# RFID_CU_Schematic.net
KiCad netlist of a schematic drawn in Altium Designer
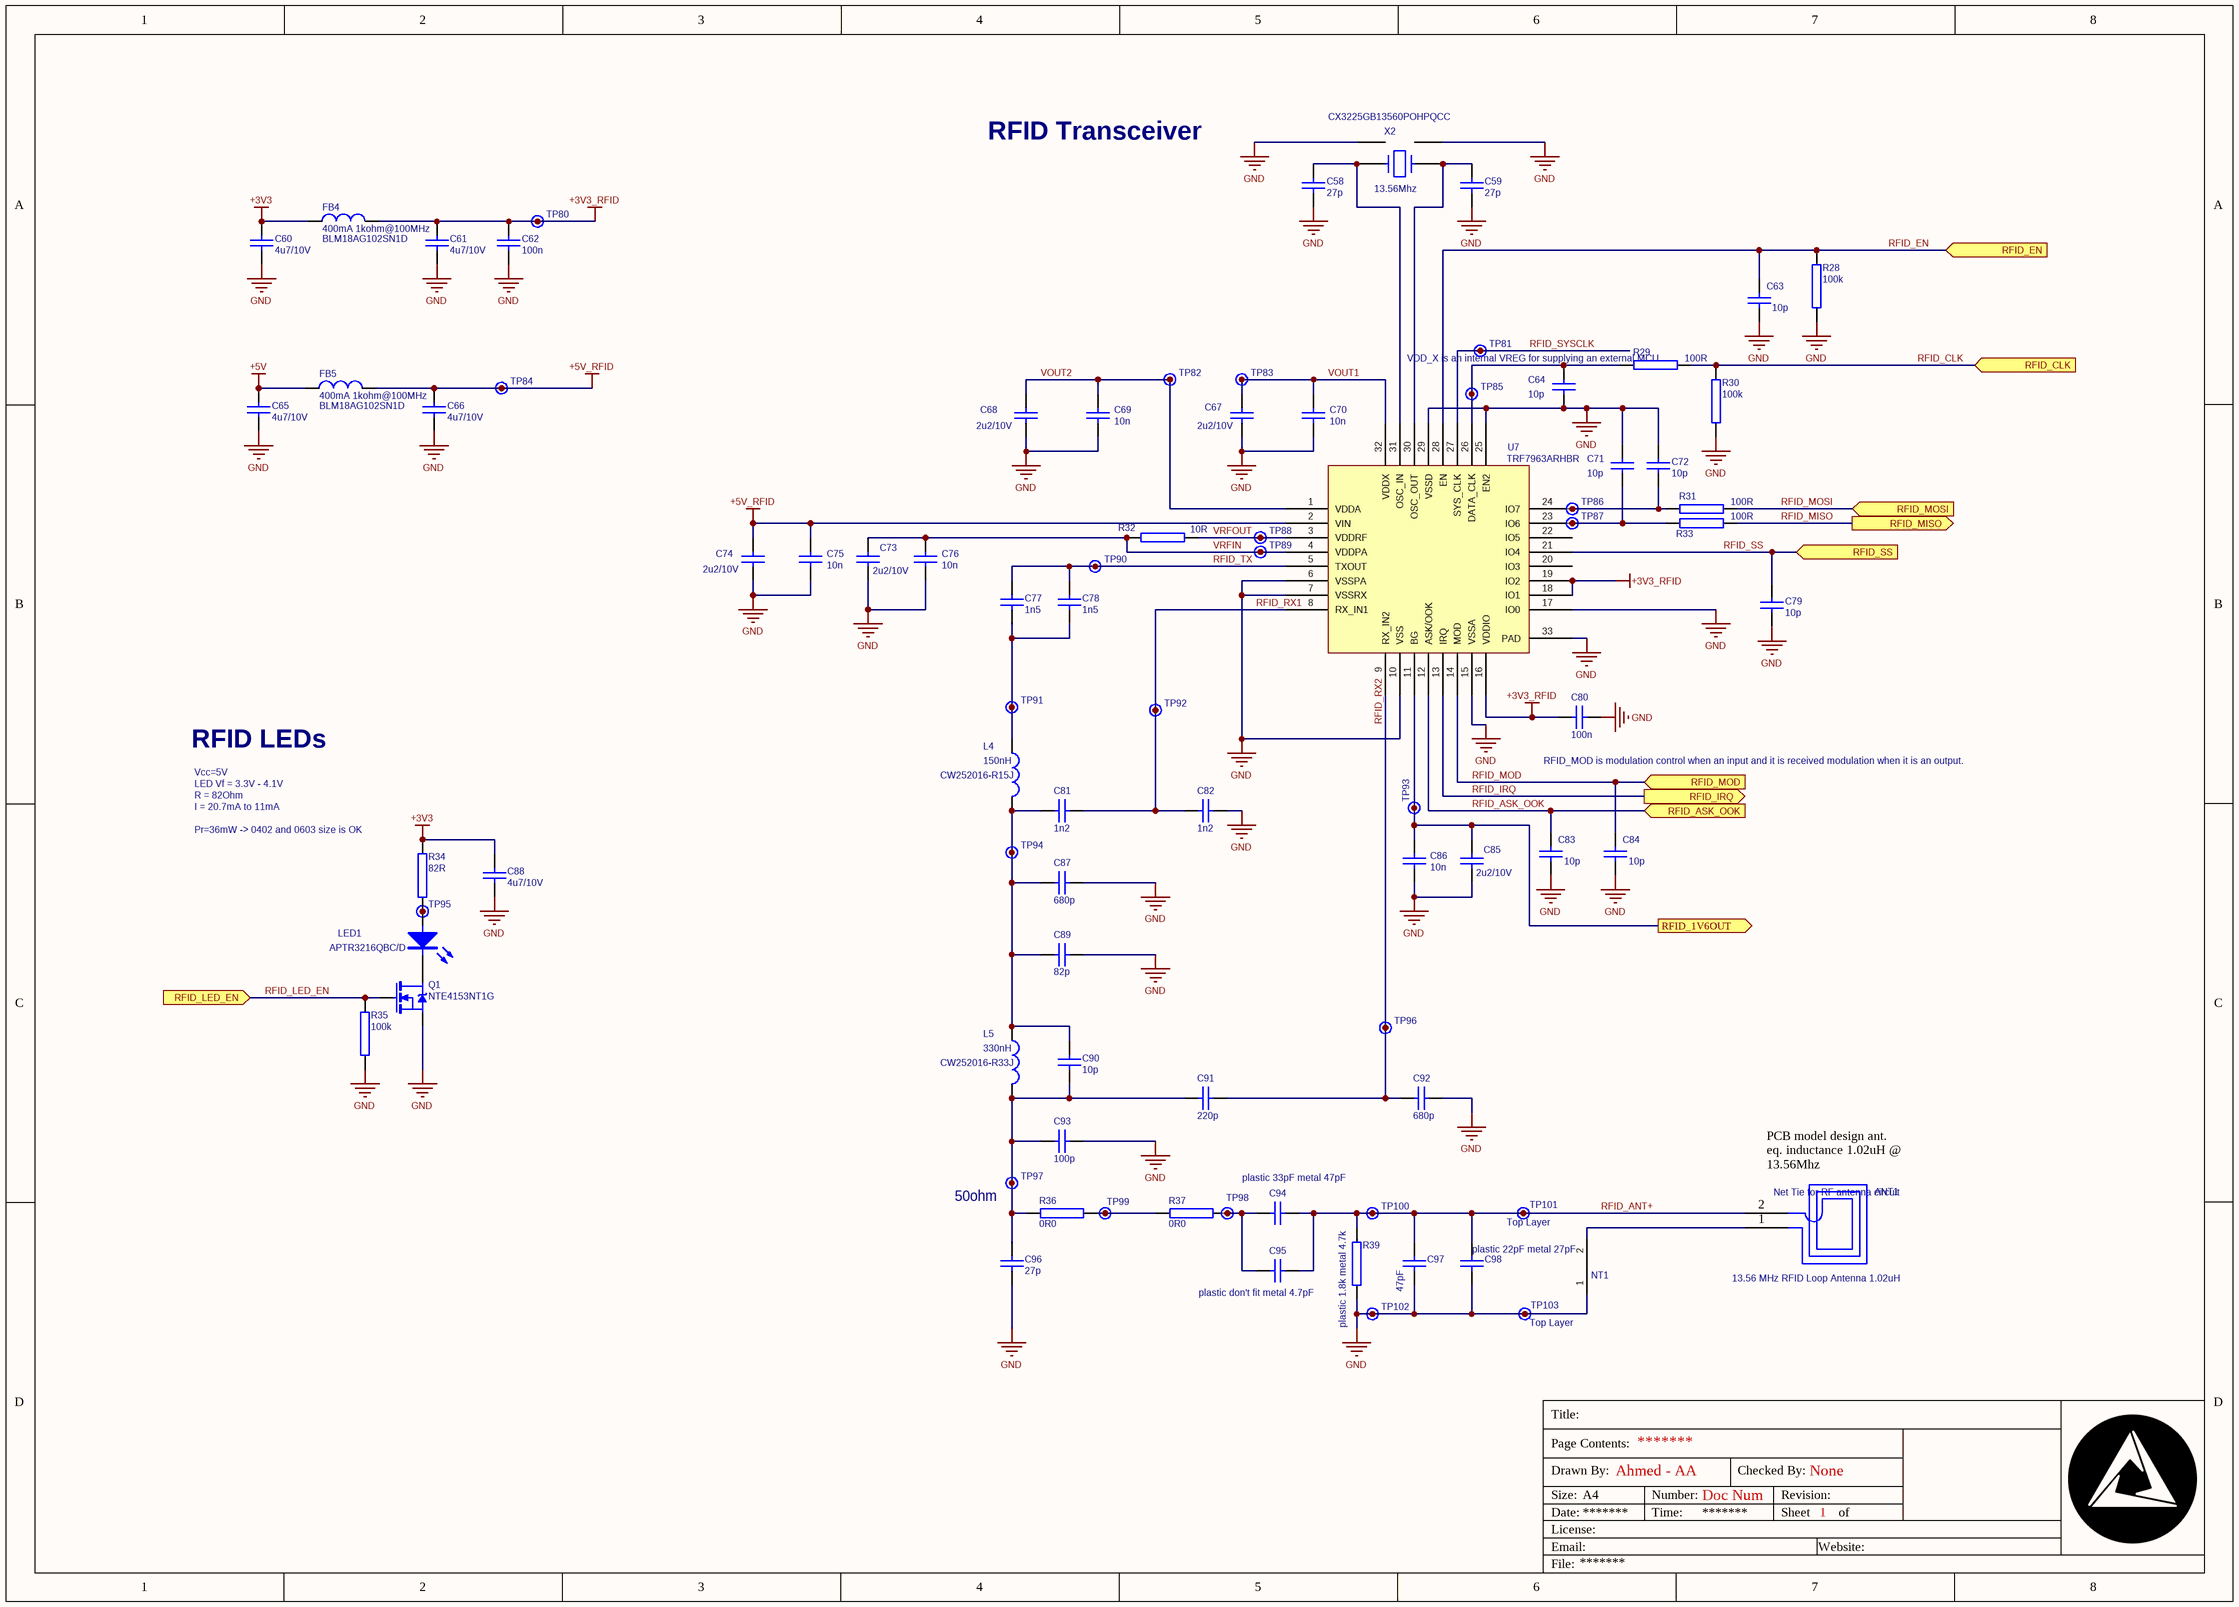
[diagram p0: RFID_CU Schematic.SchDoc]

(export (version "E")
  (design (tool "Eeschema 10.0.6"))
  (components
    (comp (ref "ANT1")
      (value "Loop Antenna")
      (footprint "RFID  Board PCB:loop_antenna")
      (description "FPC Loop Antenna")
      (fields (field (name "02 PART NUMBER") "P0000475") (field (name "12 AUTHOR") "M.Fineschi"))
      (libsource (lib "RFID Board") (part "LOOP ANT"))
    )
    (comp (ref "C58")
      (value "27p")
      (footprint "CAPC1608X09N(0603)")
      (description "Capacitor, Ceramic, 50V, Tin plated, ±1%, ±30ppm/C, C0G, 100mohm, -55°C to 125°C")
      (fields (field (name "02 PART NUMBER") "GRM1885C1H180FA01D") (field (name "12 AUTHOR") "D.Grace"))
      (libsource (lib "Miscellaneous Devices") (part "GRM1885C1H180FA01D"))
    )
    (comp (ref "C59")
      (value "27p")
      (footprint "CAPC1608X09N(0603)")
      (description "Capacitor, Ceramic, 50V, Tin plated, ±1%, ±30ppm/C, C0G, 100mohm, -55°C to 125°C")
      (fields (field (name "02 PART NUMBER") "GRM1885C1H180FA01D") (field (name "12 AUTHOR") "D.Grace"))
      (libsource (lib "Miscellaneous Devices") (part "GRM1885C1H180FA01D"))
    )
    (comp (ref "C60")
      (value "4u7/10V")
      (footprint "CAPC1608X09N(0603)")
      (description "Capacitor, Ceramic, 10V, ±10%, X5R, -55°C to 125°C")
      (fields (field (name "02 PART NUMBER") "CC0603KRX5R6BB475") (field (name "12 AUTHOR") "K.Sukumar"))
      (libsource (lib "Ingenuity Master Capacitor Schematic Library") (part "CC0603KRX5R6BB475"))
    )
    (comp (ref "C61")
      (value "4u7/10V")
      (footprint "CAPC1608X09N(0603)")
      (description "Capacitor, Ceramic, 10V, ±10%, X5R, -55°C to 125°C")
      (fields (field (name "02 PART NUMBER") "CC0603KRX5R6BB475") (field (name "12 AUTHOR") "K.Sukumar"))
      (libsource (lib "Ingenuity Master Capacitor Schematic Library") (part "CC0603KRX5R6BB475"))
    )
    (comp (ref "C62")
      (value "100n")
      (footprint "CAPC1608X09N(0603)")
      (description "Capacitor, Ceramic, 50V, ±10%, X7R, -55°C to 125°C")
      (fields (field (name "02 PART NUMBER") "GRM188R71H104KA93D") (field (name "12 AUTHOR") "D.Grace"))
      (libsource (lib "Ingenuity Master Capacitor Schematic Library") (part "GRM188R71H104KA93D"))
    )
    (comp (ref "C63")
      (value "10p")
      (footprint "CAPC1608X09N(0603)")
      (description "Capacitor, Ceramic, 50V, ±5%, NP0, -55°C to 125°C")
      (fields (field (name "02 PART NUMBER") "GQM1885C1H100JB01D") (field (name "12 AUTHOR") "M.Fineschi"))
      (libsource (lib "D0001310 Trophon EPR GUI Carrier Board Schematic Library (1_0)") (part "GQM1885C1H100JB01D"))
    )
    (comp (ref "C64")
      (value "10p")
      (footprint "CAPC1608X09N(0603)")
      (description "Capacitor, Ceramic, 50V, ±5%, NP0, -55°C to 125°C")
      (fields (field (name "02 PART NUMBER") "GQM1885C1H100JB01D") (field (name "12 AUTHOR") "M.Fineschi"))
      (libsource (lib "D0001310 Trophon EPR GUI Carrier Board Schematic Library (1_0)") (part "GQM1885C1H100JB01D"))
    )
    (comp (ref "C65")
      (value "4u7/10V")
      (footprint "CAPC1608X09N(0603)")
      (description "Capacitor, Ceramic, 10V, ±10%, X5R, -55°C to 125°C")
      (fields (field (name "02 PART NUMBER") "CC0603KRX5R6BB475") (field (name "12 AUTHOR") "K.Sukumar"))
      (libsource (lib "Ingenuity Master Capacitor Schematic Library") (part "CC0603KRX5R6BB475"))
    )
    (comp (ref "C66")
      (value "4u7/10V")
      (footprint "CAPC1608X09N(0603)")
      (description "Capacitor, Ceramic, 10V, ±10%, X5R, -55°C to 125°C")
      (fields (field (name "02 PART NUMBER") "CC0603KRX5R6BB475") (field (name "12 AUTHOR") "K.Sukumar"))
      (libsource (lib "Ingenuity Master Capacitor Schematic Library") (part "CC0603KRX5R6BB475"))
    )
    (comp (ref "C67")
      (value "2u2/10V")
      (footprint "CAPC1608X09N(0603)")
      (description "Capacitor, Ceramic, 10V, ±10%, X7R, -55°C to 125°C")
      (fields (field (name "02 PART NUMBER") "GRM188R71A225KE15D") (field (name "12 AUTHOR") "D.Grace"))
      (libsource (lib "Ingenuity Master Capacitor Schematic Library") (part "GRM188R71A225KE15D"))
    )
    (comp (ref "C68")
      (value "2u2/10V")
      (footprint "CAPC1608X09N(0603)")
      (description "Capacitor, Ceramic, 10V, ±10%, X7R, -55°C to 125°C")
      (fields (field (name "02 PART NUMBER") "GRM188R71A225KE15D") (field (name "12 AUTHOR") "D.Grace"))
      (libsource (lib "Ingenuity Master Capacitor Schematic Library") (part "GRM188R71A225KE15D"))
    )
    (comp (ref "C69")
      (value "10n")
      (footprint "CAPC1608X09N(0603)")
      (description "Capacitor, Ceramic, 50V, ±10%, X7R, -55°C to 125°C")
      (fields (field (name "02 PART NUMBER") "GRM188R71H103KA01D") (field (name "12 AUTHOR") "D.Grace"))
      (libsource (lib "Ingenuity Master Capacitor Schematic Library") (part "GRM188R71H103KA01D"))
    )
    (comp (ref "C70")
      (value "10n")
      (footprint "CAPC1608X09N(0603)")
      (description "Capacitor, Ceramic, 50V, ±10%, X7R, -55°C to 125°C")
      (fields (field (name "02 PART NUMBER") "GRM188R71H103KA01D") (field (name "12 AUTHOR") "D.Grace"))
      (libsource (lib "Ingenuity Master Capacitor Schematic Library") (part "GRM188R71H103KA01D"))
    )
    (comp (ref "C71")
      (value "10p")
      (footprint "CAPC1608X09N(0603)")
      (description "Capacitor, Ceramic, 50V, ±5%, NP0, -55°C to 125°C")
      (fields (field (name "02 PART NUMBER") "GQM1885C1H100JB01D") (field (name "12 AUTHOR") "M.Fineschi"))
      (libsource (lib "D0001310 Trophon EPR GUI Carrier Board Schematic Library (1_0)") (part "GQM1885C1H100JB01D"))
    )
    (comp (ref "C72")
      (value "10p")
      (footprint "CAPC1608X09N(0603)")
      (description "Capacitor, Ceramic, 50V, ±5%, NP0, -55°C to 125°C")
      (fields (field (name "02 PART NUMBER") "GQM1885C1H100JB01D") (field (name "12 AUTHOR") "M.Fineschi"))
      (libsource (lib "D0001310 Trophon EPR GUI Carrier Board Schematic Library (1_0)") (part "GQM1885C1H100JB01D"))
    )
    (comp (ref "C73")
      (value "2u2/10V")
      (footprint "CAPC1608X09N(0603)")
      (description "Capacitor, Ceramic, 10V, ±10%, X7R, -55°C to 125°C")
      (fields (field (name "02 PART NUMBER") "GRM188R71A225KE15D") (field (name "12 AUTHOR") "D.Grace"))
      (libsource (lib "Ingenuity Master Capacitor Schematic Library") (part "GRM188R71A225KE15D"))
    )
    (comp (ref "C74")
      (value "2u2/10V")
      (footprint "CAPC1608X09N(0603)")
      (description "Capacitor, Ceramic, 10V, ±10%, X7R, -55°C to 125°C")
      (fields (field (name "02 PART NUMBER") "GRM188R71A225KE15D") (field (name "12 AUTHOR") "D.Grace"))
      (libsource (lib "Ingenuity Master Capacitor Schematic Library") (part "GRM188R71A225KE15D"))
    )
    (comp (ref "C75")
      (value "10n")
      (footprint "CAPC1608X09N(0603)")
      (description "Capacitor, Ceramic, 50V, ±10%, X7R, -55°C to 125°C")
      (fields (field (name "02 PART NUMBER") "GRM188R71H103KA01D") (field (name "12 AUTHOR") "D.Grace"))
      (libsource (lib "Ingenuity Master Capacitor Schematic Library") (part "GRM188R71H103KA01D"))
    )
    (comp (ref "C76")
      (value "10n")
      (footprint "CAPC1608X09N(0603)")
      (description "Capacitor, Ceramic, 50V, ±10%, X7R, -55°C to 125°C")
      (fields (field (name "02 PART NUMBER") "GRM188R71H103KA01D") (field (name "12 AUTHOR") "D.Grace"))
      (libsource (lib "Ingenuity Master Capacitor Schematic Library") (part "GRM188R71H103KA01D"))
    )
    (comp (ref "C77")
      (value "1n5")
      (footprint "CAPC1608X09N(0603)")
      (description "Capacitor, Ceramic, 50V, ±10%, X7R, -55°C to 125°C")
      (fields (field (name "02 PART NUMBER") "GRM188R71H152KA01D") (field (name "12 AUTHOR") "M.Fineschi"))
      (libsource (lib "D0001310 Trophon EPR GUI Carrier Board Schematic Library (1_0)") (part "GRM188R71H152KA01D"))
    )
    (comp (ref "C78")
      (value "1n5")
      (footprint "CAPC1608X09N(0603)")
      (description "Capacitor, Ceramic, 50V, ±10%, X7R, -55°C to 125°C")
      (fields (field (name "02 PART NUMBER") "GRM188R71H152KA01D") (field (name "12 AUTHOR") "M.Fineschi"))
      (libsource (lib "D0001310 Trophon EPR GUI Carrier Board Schematic Library (1_0)") (part "GRM188R71H152KA01D"))
    )
    (comp (ref "C79")
      (value "10p")
      (footprint "CAPC1608X09N(0603)")
      (description "Capacitor, Ceramic, 50V, ±5%, NP0, -55°C to 125°C")
      (fields (field (name "02 PART NUMBER") "GQM1885C1H100JB01D") (field (name "12 AUTHOR") "M.Fineschi"))
      (libsource (lib "D0001310 Trophon EPR GUI Carrier Board Schematic Library (1_0)") (part "GQM1885C1H100JB01D"))
    )
    (comp (ref "C80")
      (value "100n")
      (footprint "CAPC1608X09N(0603)")
      (description "Capacitor, Ceramic, 50V, ±10%, X7R, -55°C to 125°C")
      (fields (field (name "02 PART NUMBER") "GRM188R71H104KA93D") (field (name "12 AUTHOR") "D.Grace"))
      (libsource (lib "Ingenuity Master Capacitor Schematic Library") (part "GRM188R71H104KA93D"))
    )
    (comp (ref "C81")
      (value "1n2")
      (footprint "CAPC1608X09N(0603)")
      (description "Capacitor, Ceramic, 50V, ±10%, X7R, -55°C to 125°C")
      (fields (field (name "02 PART NUMBER") "GRM188R71H122KA01D") (field (name "12 AUTHOR") "M.Fineschi"))
      (libsource (lib "D0001310 Trophon EPR GUI Carrier Board Schematic Library (1_0)") (part "GRM188R71H122KA01D"))
    )
    (comp (ref "C82")
      (value "1n2")
      (footprint "CAPC1608X09N(0603)")
      (description "Capacitor, Ceramic, 50V, ±10%, X7R, -55°C to 125°C")
      (fields (field (name "02 PART NUMBER") "GRM188R71H122KA01D") (field (name "12 AUTHOR") "M.Fineschi"))
      (libsource (lib "D0001310 Trophon EPR GUI Carrier Board Schematic Library (1_0)") (part "GRM188R71H122KA01D"))
    )
    (comp (ref "C83")
      (value "10p")
      (footprint "CAPC1608X09N(0603)")
      (description "Capacitor, Ceramic, 50V, ±5%, NP0, -55°C to 125°C")
      (fields (field (name "02 PART NUMBER") "GQM1885C1H100JB01D") (field (name "12 AUTHOR") "M.Fineschi"))
      (libsource (lib "D0001310 Trophon EPR GUI Carrier Board Schematic Library (1_0)") (part "GQM1885C1H100JB01D"))
    )
    (comp (ref "C84")
      (value "10p")
      (footprint "CAPC1608X09N(0603)")
      (description "Capacitor, Ceramic, 50V, ±5%, NP0, -55°C to 125°C")
      (fields (field (name "02 PART NUMBER") "GQM1885C1H100JB01D") (field (name "12 AUTHOR") "M.Fineschi"))
      (libsource (lib "D0001310 Trophon EPR GUI Carrier Board Schematic Library (1_0)") (part "GQM1885C1H100JB01D"))
    )
    (comp (ref "C85")
      (value "2u2/10V")
      (footprint "CAPC1608X09N(0603)")
      (description "Capacitor, Ceramic, 10V, ±10%, X7R, -55°C to 125°C")
      (fields (field (name "02 PART NUMBER") "GRM188R71A225KE15D") (field (name "12 AUTHOR") "D.Grace"))
      (libsource (lib "Ingenuity Master Capacitor Schematic Library") (part "GRM188R71A225KE15D"))
    )
    (comp (ref "C86")
      (value "10n")
      (footprint "CAPC1608X09N(0603)")
      (description "Capacitor, Ceramic, 50V, ±10%, X7R, -55°C to 125°C")
      (fields (field (name "02 PART NUMBER") "GRM188R71H103KA01D") (field (name "12 AUTHOR") "D.Grace"))
      (libsource (lib "Ingenuity Master Capacitor Schematic Library") (part "GRM188R71H103KA01D"))
    )
    (comp (ref "C87")
      (value "680p")
      (footprint "CAPC1608X09N(0603)")
      (description "Capacitor, Ceramic, 50V, ±10%, X7R, -55°C to 125°C")
      (fields (field (name "02 PART NUMBER") "GRM188R71H681KA01D") (field (name "12 AUTHOR") "M.Fineschi"))
      (libsource (lib "D0001310 Trophon EPR GUI Carrier Board Schematic Library (1_0)") (part "GRM188R71H681KA01D"))
    )
    (comp (ref "C88")
      (value "4u7/10V")
      (footprint "CAPC1608X09N(0603)")
      (description "Capacitor, Ceramic, 10V, ±10%, X5R, -55°C to 125°C")
      (fields (field (name "02 PART NUMBER") "CC0603KRX5R6BB475") (field (name "12 AUTHOR") "K.Sukumar"))
      (libsource (lib "Ingenuity Master Capacitor Schematic Library") (part "CC0603KRX5R6BB475"))
    )
    (comp (ref "C89")
      (value "82p")
      (footprint "CAPC1608X09N(0603)")
      (description "Capacitor, Ceramic, 50V, ±5%, NP0, -55°C to 125°C")
      (fields (field (name "02 PART NUMBER") "GRM1885C1H820JA01D") (field (name "12 AUTHOR") "M.Fineschi"))
      (libsource (lib "D0001310 Trophon EPR GUI Carrier Board Schematic Library (1_0)") (part "GRM1885C1H820JA01D"))
    )
    (comp (ref "C90")
      (value "10p")
      (footprint "CAPC1608X09N(0603)")
      (description "Capacitor, Ceramic, 50V, ±5%, NP0, -55°C to 125°C")
      (fields (field (name "02 PART NUMBER") "GQM1885C1H100JB01D") (field (name "12 AUTHOR") "M.Fineschi"))
      (libsource (lib "D0001310 Trophon EPR GUI Carrier Board Schematic Library (1_0)") (part "GQM1885C1H100JB01D"))
    )
    (comp (ref "C91")
      (value "220p")
      (footprint "CAPC1608X09N(0603)")
      (description "Capacitor, Ceramic, 50V, ±10%, X7R, -55°C to 125°C")
      (fields (field (name "02 PART NUMBER") "GRM188R71H221KA01D") (field (name "12 AUTHOR") "M.Fineschi"))
      (libsource (lib "D0001310 Trophon EPR GUI Carrier Board Schematic Library (1_0)") (part "GRM188R71H221KA01D"))
    )
    (comp (ref "C92")
      (value "680p")
      (footprint "CAPC1608X09N(0603)")
      (description "Capacitor, Ceramic, 50V, ±10%, X7R, -55°C to 125°C")
      (fields (field (name "02 PART NUMBER") "GRM188R71H681KA01D") (field (name "12 AUTHOR") "M.Fineschi"))
      (libsource (lib "D0001310 Trophon EPR GUI Carrier Board Schematic Library (1_0)") (part "GRM188R71H681KA01D"))
    )
    (comp (ref "C93")
      (value "100p")
      (footprint "CAPC1608X09N(0603)")
      (description "Capacitor, Ceramic, 50V, ±5%, C0G NP0, -55°C to 125°C")
      (fields (field (name "02 PART NUMBER") "GRM1885C1H101JA01D") (field (name "12 AUTHOR") "D.Grace"))
      (libsource (lib "Ingenuity Master Capacitor Schematic Library") (part "GRM1885C1H101JA01D"))
    )
    (comp (ref "C94")
      (value "plastic 33pF metal 47pF")
      (footprint "CAPC1608X09N(0603)")
      (description "Capacitor, Ceramic, 50V, ±5%, NP0, -55°C to 125°C")
      (fields (field (name "02 PART NUMBER") "GRM1885C1H470JA01D") (field (name "12 AUTHOR") "M.Fineschi"))
      (libsource (lib "D0001310 Trophon EPR GUI Carrier Board Schematic Library (1_0)") (part "GRM1885C1H470JA01D"))
    )
    (comp (ref "C95")
      (value "plastic don't fit metal 4.7pF")
      (footprint "CAPC1608X09N(0603)")
      (description "Capacitor, Ceramic, 50V, ±5%, NP0, -55°C to 125°C")
      (fields (field (name "02 PART NUMBER") "GQM1885C1H100JB01D") (field (name "12 AUTHOR") "M.Fineschi"))
      (libsource (lib "D0001310 Trophon EPR GUI Carrier Board Schematic Library (1_0)") (part "GQM1885C1H100JB01D"))
    )
    (comp (ref "C96")
      (value "27p")
      (footprint "CAPC1608X09N(0603)")
      (description "Capacitor, Ceramic, 50V, ±5%, NP0, -55°C to 125°C")
      (fields (field (name "02 PART NUMBER") "GRM1885C1H270JA01D") (field (name "12 AUTHOR") "M.Fineschi"))
      (libsource (lib "D0001310 Trophon EPR GUI Carrier Board Schematic Library (1_0)") (part "GRM1885C1H270JA01D"))
    )
    (comp (ref "C97")
      (value "47pF")
      (footprint "CAPC1608X09N(0603)")
      (description "Capacitor, Ceramic, 50V, ±5%, NP0, -55°C to 125°C")
      (fields (field (name "02 PART NUMBER") "GRM1885C1H820JA01D") (field (name "12 AUTHOR") "M.Fineschi"))
      (libsource (lib "D0001310 Trophon EPR GUI Carrier Board Schematic Library (1_0)") (part "GRM1885C1H820JA01D"))
    )
    (comp (ref "C98")
      (value "plastic 22pF metal 27pF")
      (footprint "CAPC1608X09N(0603)")
      (description "Capacitor, Ceramic, 50V, ±5%, C0G NP0, -55°C to 125°C")
      (fields (field (name "02 PART NUMBER") "GRM1885C1H101JA01D") (field (name "12 AUTHOR") "D.Grace"))
      (libsource (lib "Ingenuity Master Capacitor Schematic Library") (part "GRM1885C1H101JA01D"))
    )
    (comp (ref "FB4")
      (value "400mA 1kohm@100MHz")
      (footprint "RESC1608X06N")
      (description "Ferrite Bead, 1kohm@100MHz, 400mA, 500mohm, -55 to 125C")
      (fields (field (name "02 PART NUMBER") "BLM18AG102SN1D") (field (name "12 AUTHOR") "M.Fineschi"))
      (libsource (lib "D0000174 Puck Charger Schematic Library (1_6)") (part "BLM18AG102SN1D"))
    )
    (comp (ref "FB5")
      (value "400mA 1kohm@100MHz")
      (footprint "RESC1608X06N")
      (description "Ferrite Bead, 1kohm@100MHz, 400mA, 500mohm, -55 to 125C")
      (fields (field (name "02 PART NUMBER") "BLM18AG102SN1D") (field (name "12 AUTHOR") "M.Fineschi"))
      (libsource (lib "D0000174 Puck Charger Schematic Library (1_6)") (part "BLM18AG102SN1D"))
    )
    (comp (ref "L4")
      (value "150nH")
      (footprint "CW252016")
      (description "Inductor, 150nH , I = 500mA, 220 mOhm, SRF 850MHz, ±5%")
      (fields
        (field (name "02 PART NUMBER") "CW252016-R15J")
        (field (name "12 AUTHOR") "D.Grace")
        (field (name "13 REVIEWED BY") "P.Moutzouris")
      )
      (libsource (lib "Ingenuity Master Inductors Schematic Library") (part "CW252016-R15J_PA"))
    )
    (comp (ref "L5")
      (value "330nH")
      (footprint "CW252016")
      (description "Inductor, 330nH , I = 500mA, 900 mOhm, SRF 570MHz, ±5%")
      (fields
        (field (name "02 PART NUMBER") "CW252016-R33J")
        (field (name "12 AUTHOR") "D.Grace")
        (field (name "13 REVIEWED BY") "P.Moutzouris")
      )
      (libsource (lib "Ingenuity Master Inductors Schematic Library") (part "CW252016-R33J_PA"))
    )
    (comp (ref "LED1")
      (value "APTR3216QBC/D")
      (footprint "APTR3216QBC/D")
      (description "LED, TopEntry, Blue, 4000mcd, 20mA, Vf=3V3")
      (fields (field (name "12 AUTHOR") "M.Fineschi"))
      (libsource (lib "D0001310 Trophon EPR GUI Carrier Board Altium Project (1_4)") (part "KPTR-3216ZGC"))
    )
    (comp (ref "NT1")
      (value "Net Tie")
      (footprint "0.15mm Net Tie")
      (libsource (lib "D0001231 Lock-It Smart Cabinet Panel Schematic Library") (part "Net Tie"))
    )
    (comp (ref "Q1")
      (value "NTE4153NT1G")
      (footprint "SC-89")
      (description "MOSFET, N-Channel, Logic Level, 0.5Ohm @ 1.5V, Vds 50V, Id 915mA, 300mW")
      (fields (field (name "12 AUTHOR") "D.Grace"))
      (libsource (lib "Ingenuity Master Transistors Schematic Library") (part "NTE4153NT1G"))
    )
    (comp (ref "R28")
      (value "100k")
      (footprint "RESC1608X06N(0603)")
      (description "Resistor, Thick Film, 0.1W, ±1%, ±100ppm/°C")
      (fields
        (field (name "02 PART NUMBER") "RC0603FR-07100KL")
        (field (name "13 REVIEWED BY") "P.Moutzouris")
        (field (name "12 AUTHOR") "D.Grace")
      )
      (libsource (lib "Ingenuity Master Resistor 0603 Schematic Library") (part "RC0603FR-07100KL"))
    )
    (comp (ref "R29")
      (value "100R")
      (footprint "RESC1608X06N(0603)")
      (description "Resistor, Thick Film, 0.1W, ±1%, ±100ppm/°C")
      (fields
        (field (name "02 PART NUMBER") "RC0603FR-07100RL")
        (field (name "13 REVIEWED BY") "P.Moutzouris")
        (field (name "12 AUTHOR") "D.Grace")
      )
      (libsource (lib "Ingenuity Master Resistor 0603 Schematic Library") (part "RC0603FR-07100RL"))
    )
    (comp (ref "R30")
      (value "100k")
      (footprint "RESC1608X06N(0603)")
      (description "Resistor, Thick Film, 0.1W, ±1%, ±100ppm/°C")
      (fields
        (field (name "02 PART NUMBER") "RC0603FR-07100KL")
        (field (name "13 REVIEWED BY") "P.Moutzouris")
        (field (name "12 AUTHOR") "D.Grace")
      )
      (libsource (lib "Ingenuity Master Resistor 0603 Schematic Library") (part "RC0603FR-07100KL"))
    )
    (comp (ref "R31")
      (value "100R")
      (footprint "RESC1608X06N(0603)")
      (description "Resistor, Thick Film, 0.1W, ±1%, ±100ppm/°C")
      (fields
        (field (name "02 PART NUMBER") "RC0603FR-07100RL")
        (field (name "13 REVIEWED BY") "P.Moutzouris")
        (field (name "12 AUTHOR") "D.Grace")
      )
      (libsource (lib "Ingenuity Master Resistor 0603 Schematic Library") (part "RC0603FR-07100RL"))
    )
    (comp (ref "R32")
      (value "10R")
      (footprint "RESC1608X06N(0603)")
      (description "Resistor, Thick Film, 0.1W, ±1%, ±100ppm/°C")
      (fields (field (name "02 PART NUMBER") "RC0603FR-0710RL") (field (name "12 AUTHOR") "M.Fineschi"))
      (libsource (lib "D0001310 Trophon EPR GUI Carrier Board Schematic Library (1_0)") (part "RC0603FR-0710RL"))
    )
    (comp (ref "R33")
      (value "100R")
      (footprint "RESC1608X06N(0603)")
      (description "Resistor, Thick Film, 0.1W, ±1%, ±100ppm/°C")
      (fields
        (field (name "02 PART NUMBER") "RC0603FR-07100RL")
        (field (name "13 REVIEWED BY") "P.Moutzouris")
        (field (name "12 AUTHOR") "D.Grace")
      )
      (libsource (lib "Ingenuity Master Resistor 0603 Schematic Library") (part "RC0603FR-07100RL"))
    )
    (comp (ref "R34")
      (value "82R")
      (footprint "RESC1608X06N(0603)")
      (description "Resistor, Thick Film, 0.1W, ±1%, ±100ppm/°C")
      (fields
        (field (name "02 PART NUMBER") "RC0603FR-0782RL")
        (field (name "13 REVIEWED BY") "P.Moutzouris")
        (field (name "12 AUTHOR") "D.Grace")
      )
      (libsource (lib "D0001310 Trophon EPR GUI Carrier Board Altium Project (1_4)") (part "RC0603FR-0782RL"))
    )
    (comp (ref "R35")
      (value "100k")
      (footprint "RESC1608X06N(0603)")
      (description "Resistor, Thick Film, 0.1W, ±1%, ±100ppm/°C")
      (fields
        (field (name "02 PART NUMBER") "RC0603FR-07100KL")
        (field (name "13 REVIEWED BY") "P.Moutzouris")
        (field (name "12 AUTHOR") "D.Grace")
      )
      (libsource (lib "Ingenuity Master Resistor 0603 Schematic Library") (part "RC0603FR-07100KL"))
    )
    (comp (ref "R36")
      (value "0R0")
      (footprint "RESC1608X06N(0603)")
      (description "Resistor, Thick Film, 0.1W, ±1%, ±100ppm/°C")
      (fields
        (field (name "02 PART NUMBER") "RC1608J000CS")
        (field (name "13 REVIEWED BY") "P.Moutzouris")
        (field (name "12 AUTHOR") "K.Sukumar")
      )
      (libsource (lib "Ingenuity Master Resistor 0603 Schematic Library") (part "RC1608J000CS"))
    )
    (comp (ref "R37")
      (value "0R0")
      (footprint "RESC1608X06N(0603)")
      (description "Resistor, Thick Film, 0.1W, ±1%, ±100ppm/°C")
      (fields
        (field (name "02 PART NUMBER") "RC1608J000CS")
        (field (name "13 REVIEWED BY") "P.Moutzouris")
        (field (name "12 AUTHOR") "K.Sukumar")
      )
      (libsource (lib "Ingenuity Master Resistor 0603 Schematic Library") (part "RC1608J000CS"))
    )
    (comp (ref "R39")
      (value "plastic 1.8k metal 4.7k")
      (footprint "RESC1608X06N(0603)")
      (description "Resistor, Thick Film, 0.1W, ±1%, ±100ppm/°C")
      (fields
        (field (name "02 PART NUMBER") "RC0603FR-071KL")
        (field (name "13 REVIEWED BY") "P.Moutzouris")
        (field (name "12 AUTHOR") "D.Grace")
      )
      (libsource (lib "Ingenuity Master Resistor 0603 Schematic Library") (part "RC0603FR-071KL"))
    )
    (comp (ref "TP80")
      (value "LFX_P")
      (footprint "Test Point 1mm")
      (description "Test Point")
      (fields (field (name "12 AUTHOR") "D.Grace"))
      (libsource (lib "Mesh Nebuliser Schematic Library") (part "Test Point"))
    )
    (comp (ref "TP81")
      (value "LFX_P")
      (footprint "Test Point 1mm")
      (description "Test Point")
      (fields (field (name "12 AUTHOR") "D.Grace"))
      (libsource (lib "Mesh Nebuliser Schematic Library") (part "Test Point"))
    )
    (comp (ref "TP82")
      (value "LFX_P")
      (footprint "Test Point 1mm")
      (description "Test Point")
      (fields (field (name "12 AUTHOR") "D.Grace"))
      (libsource (lib "Mesh Nebuliser Schematic Library") (part "Test Point"))
    )
    (comp (ref "TP83")
      (value "LFX_P")
      (footprint "Test Point 1mm")
      (description "Test Point")
      (fields (field (name "12 AUTHOR") "D.Grace"))
      (libsource (lib "Mesh Nebuliser Schematic Library") (part "Test Point"))
    )
    (comp (ref "TP84")
      (value "LFX_P")
      (footprint "Test Point 1mm")
      (description "Test Point")
      (fields (field (name "12 AUTHOR") "D.Grace"))
      (libsource (lib "Mesh Nebuliser Schematic Library") (part "Test Point"))
    )
    (comp (ref "TP85")
      (value "LFX_P")
      (footprint "Test Point 1mm")
      (description "Test Point")
      (fields (field (name "12 AUTHOR") "D.Grace"))
      (libsource (lib "Mesh Nebuliser Schematic Library") (part "Test Point"))
    )
    (comp (ref "TP86")
      (value "LFX_P")
      (footprint "Test Point 1mm")
      (description "Test Point")
      (fields (field (name "12 AUTHOR") "D.Grace"))
      (libsource (lib "Mesh Nebuliser Schematic Library") (part "Test Point"))
    )
    (comp (ref "TP87")
      (value "LFX_P")
      (footprint "Test Point 1mm")
      (description "Test Point")
      (fields (field (name "12 AUTHOR") "D.Grace"))
      (libsource (lib "Mesh Nebuliser Schematic Library") (part "Test Point"))
    )
    (comp (ref "TP88")
      (value "LFX_P")
      (footprint "Test Point 1mm")
      (description "Test Point")
      (fields (field (name "12 AUTHOR") "D.Grace"))
      (libsource (lib "Mesh Nebuliser Schematic Library") (part "Test Point"))
    )
    (comp (ref "TP89")
      (value "LFX_P")
      (footprint "Test Point 1mm")
      (description "Test Point")
      (fields (field (name "12 AUTHOR") "D.Grace"))
      (libsource (lib "Mesh Nebuliser Schematic Library") (part "Test Point"))
    )
    (comp (ref "TP90")
      (value "LFX_P")
      (footprint "Test Point 1mm")
      (description "Test Point")
      (fields (field (name "12 AUTHOR") "D.Grace"))
      (libsource (lib "Mesh Nebuliser Schematic Library") (part "Test Point"))
    )
    (comp (ref "TP91")
      (value "LFX_P")
      (footprint "Test Point 1mm")
      (description "Test Point")
      (fields (field (name "12 AUTHOR") "D.Grace"))
      (libsource (lib "Mesh Nebuliser Schematic Library") (part "Test Point"))
    )
    (comp (ref "TP92")
      (value "LFX_P")
      (footprint "Test Point 1mm")
      (description "Test Point")
      (fields (field (name "12 AUTHOR") "D.Grace"))
      (libsource (lib "Mesh Nebuliser Schematic Library") (part "Test Point"))
    )
    (comp (ref "TP93")
      (value "LFX_P")
      (footprint "Test Point 1mm")
      (description "Test Point")
      (fields (field (name "12 AUTHOR") "D.Grace"))
      (libsource (lib "Mesh Nebuliser Schematic Library") (part "Test Point"))
    )
    (comp (ref "TP94")
      (value "LFX_P")
      (footprint "Test Point 1mm")
      (description "Test Point")
      (fields (field (name "12 AUTHOR") "D.Grace"))
      (libsource (lib "Mesh Nebuliser Schematic Library") (part "Test Point"))
    )
    (comp (ref "TP95")
      (value "LFX_P")
      (footprint "Test Point 1mm")
      (description "Test Point")
      (fields (field (name "12 AUTHOR") "D.Grace"))
      (libsource (lib "Mesh Nebuliser Schematic Library") (part "Test Point"))
    )
    (comp (ref "TP96")
      (value "LFX_P")
      (footprint "Test Point 1mm")
      (description "Test Point")
      (fields (field (name "12 AUTHOR") "D.Grace"))
      (libsource (lib "Mesh Nebuliser Schematic Library") (part "Test Point"))
    )
    (comp (ref "TP97")
      (value "50ohm")
      (footprint "Test Point 1mm")
      (description "Test Point")
      (fields (field (name "12 AUTHOR") "D.Grace"))
      (libsource (lib "Mesh Nebuliser Schematic Library") (part "Test Point"))
    )
    (comp (ref "TP98")
      (value "LFX_P")
      (footprint "Test Point 1mm")
      (description "Test Point")
      (fields (field (name "12 AUTHOR") "D.Grace"))
      (libsource (lib "Mesh Nebuliser Schematic Library") (part "Test Point"))
    )
    (comp (ref "TP99")
      (value "LFX_P")
      (footprint "Test Point 1mm")
      (description "Test Point")
      (fields (field (name "12 AUTHOR") "D.Grace"))
      (libsource (lib "Mesh Nebuliser Schematic Library") (part "Test Point"))
    )
    (comp (ref "TP100")
      (value "LFX_P")
      (footprint "Test Point 1mm")
      (description "Test Point")
      (fields (field (name "12 AUTHOR") "D.Grace"))
      (libsource (lib "Mesh Nebuliser Schematic Library") (part "Test Point"))
    )
    (comp (ref "TP101")
      (value "LFX_P")
      (footprint "Test Point 1mm")
      (description "Test Point")
      (fields (field (name "NOTES") "Top Layer") (field (name "12 AUTHOR") "D.Grace"))
      (libsource (lib "Mesh Nebuliser Schematic Library") (part "Test Point"))
    )
    (comp (ref "TP102")
      (value "LFX_P")
      (footprint "Test Point 1mm")
      (description "Test Point")
      (fields (field (name "12 AUTHOR") "D.Grace"))
      (libsource (lib "Mesh Nebuliser Schematic Library") (part "Test Point"))
    )
    (comp (ref "TP103")
      (value "LFX_P")
      (footprint "Test Point 1mm")
      (description "Test Point")
      (fields (field (name "NOTES") "Top Layer") (field (name "12 AUTHOR") "D.Grace"))
      (libsource (lib "Mesh Nebuliser Schematic Library") (part "Test Point"))
    )
    (comp (ref "U7")
      (value "TRF7963ARHBR")
      (footprint "QFN-32")
      (description "RFID/NFC AFE 13.56MHZ")
      (fields (field (name "12 AUTHOR") "K.Sukumar"))
      (libsource (lib "D0001310 Trophon EPR GUI Carrier Board Schematic Library (1_0)") (part "TRF7963ARHBR"))
    )
    (comp (ref "X2")
      (value "13.56Mhz")
      (footprint "CX3225GB13560D0HEQCC")
      (description "Crystal, 13.56Mhz, 18pF, +-30ppm, 50Ohm, Fundamental")
      (fields (field (name "02 PART NUMBER") "CX3225GB13560POHPQCC") (field (name "12 AUTHOR") "J.Orhan"))
      (libsource (lib "D0001310 Trophon EPR GUI Carrier Board Schematic Library (1_0)") (part "7A-13.560MAAJ-T"))
    )
  )
  (nets
    (net (code "1") (name "+3V3") (class "Default")
      (node (ref "C60") (pin "2") (pinfunction "2_2") (pintype "passive"))
      (node (ref "C88") (pin "2") (pinfunction "2_2") (pintype "passive"))
      (node (ref "FB4") (pin "1") (pinfunction "1_1") (pintype "passive"))
      (node (ref "R34") (pin "2") (pintype "passive"))
    )
    (net (code "2") (name "+3V3_RFID") (class "Default")
      (node (ref "C61") (pin "2") (pinfunction "2_2") (pintype "passive"))
      (node (ref "C62") (pin "2") (pinfunction "2_2") (pintype "passive"))
      (node (ref "C80") (pin "2") (pinfunction "2_2") (pintype "passive"))
      (node (ref "FB4") (pin "2") (pinfunction "2_2") (pintype "passive"))
      (node (ref "TP80") (pin "TP") (pinfunction "TP_TP") (pintype "passive"))
      (node (ref "U7") (pin "16") (pinfunction "VDDIO_16") (pintype "passive"))
      (node (ref "U7") (pin "18") (pinfunction "IO1_18") (pintype "passive"))
      (node (ref "U7") (pin "19") (pinfunction "IO2_19") (pintype "passive"))
    )
    (net (code "3") (name "+5V") (class "Default")
      (node (ref "C65") (pin "2") (pinfunction "2_2") (pintype "passive"))
      (node (ref "FB5") (pin "1") (pinfunction "1_1") (pintype "passive"))
    )
    (net (code "4") (name "+5V_RFID") (class "Default")
      (node (ref "C66") (pin "2") (pinfunction "2_2") (pintype "passive"))
      (node (ref "C74") (pin "2") (pinfunction "2_2") (pintype "passive"))
      (node (ref "C75") (pin "2") (pinfunction "2_2") (pintype "passive"))
      (node (ref "FB5") (pin "2") (pinfunction "2_2") (pintype "passive"))
      (node (ref "TP84") (pin "TP") (pinfunction "TP_TP") (pintype "passive"))
      (node (ref "U7") (pin "2") (pinfunction "VIN_2") (pintype "passive"))
    )
    (net (code "5") (name "/RFID_1V6OUT") (class "Default")
      (node (ref "C85") (pin "2") (pinfunction "2_2") (pintype "passive"))
      (node (ref "C86") (pin "2") (pinfunction "2_2") (pintype "passive"))
      (node (ref "TP93") (pin "TP") (pinfunction "TP_TP") (pintype "passive"))
      (node (ref "U7") (pin "11") (pinfunction "BG_11") (pintype "passive"))
    )
    (net (code "6") (name "/RFID_ANT+") (class "Default")
      (node (ref "C94") (pin "1") (pinfunction "1_1") (pintype "passive"))
      (node (ref "C95") (pin "1") (pinfunction "1_1") (pintype "passive"))
      (node (ref "C97") (pin "1") (pinfunction "1_1") (pintype "passive"))
      (node (ref "C98") (pin "1") (pinfunction "1_1") (pintype "passive"))
      (node (ref "R39") (pin "2") (pintype "passive"))
      (node (ref "TP100") (pin "TP") (pinfunction "TP_TP") (pintype "passive"))
      (node (ref "TP101") (pin "TP") (pinfunction "TP_TP") (pintype "passive"))
    )
    (net (code "7") (name "/RFID_ASK_OOK") (class "Default")
      (node (ref "C83") (pin "1") (pinfunction "1_1") (pintype "passive"))
      (node (ref "U7") (pin "12") (pinfunction "ASK/OOK_12") (pintype "passive"))
    )
    (net (code "8") (name "/RFID_CLK") (class "Default")
      (node (ref "R29") (pin "2") (pintype "passive"))
      (node (ref "R30") (pin "2") (pintype "passive"))
    )
    (net (code "9") (name "/RFID_EN") (class "Default")
      (node (ref "C63") (pin "1") (pinfunction "1_1") (pintype "passive"))
      (node (ref "R28") (pin "2") (pintype "passive"))
      (node (ref "U7") (pin "28") (pinfunction "EN_28") (pintype "passive"))
    )
    (net (code "10") (name "/RFID_IRQ") (class "Default")
      (node (ref "U7") (pin "13") (pinfunction "IRQ_13") (pintype "passive"))
    )
    (net (code "11") (name "/RFID_LED_EN") (class "Default")
      (node (ref "Q1") (pin "G") (pinfunction "G_G") (pintype "passive"))
      (node (ref "R35") (pin "2") (pintype "passive"))
    )
    (net (code "12") (name "/RFID_MISO") (class "Default") (node (ref "R33") (pin "2") (pintype "passive")))
    (net (code "13") (name "/RFID_MOD") (class "Default")
      (node (ref "C84") (pin "1") (pinfunction "1_1") (pintype "passive"))
      (node (ref "U7") (pin "14") (pinfunction "MOD_14") (pintype "passive"))
    )
    (net (code "14") (name "/RFID_MOSI") (class "Default") (node (ref "R31") (pin "2") (pintype "passive")))
    (net (code "15") (name "/RFID_RX1") (class "Default")
      (node (ref "C81") (pin "1") (pinfunction "1_1") (pintype "passive"))
      (node (ref "C82") (pin "2") (pinfunction "2_2") (pintype "passive"))
      (node (ref "TP92") (pin "TP") (pinfunction "TP_TP") (pintype "passive"))
      (node (ref "U7") (pin "8") (pinfunction "RX_IN1_8") (pintype "passive"))
    )
    (net (code "16") (name "/RFID_RX2") (class "Default")
      (node (ref "C91") (pin "1") (pinfunction "1_1") (pintype "passive"))
      (node (ref "C92") (pin "2") (pinfunction "2_2") (pintype "passive"))
      (node (ref "TP96") (pin "TP") (pinfunction "TP_TP") (pintype "passive"))
      (node (ref "U7") (pin "9") (pinfunction "RX_IN2_9") (pintype "passive"))
    )
    (net (code "17") (name "/RFID_SS") (class "Default")
      (node (ref "C79") (pin "1") (pinfunction "1_1") (pintype "passive"))
      (node (ref "U7") (pin "21") (pinfunction "IO4_21") (pintype "passive"))
    )
    (net (code "18") (name "/RFID_SYSCLK") (class "Default")
      (node (ref "TP81") (pin "TP") (pinfunction "TP_TP") (pintype "passive"))
      (node (ref "U7") (pin "27") (pinfunction "SYS_CLK_27") (pintype "passive"))
    )
    (net (code "19") (name "/RFID_TX") (class "Default")
      (node (ref "C77") (pin "2") (pinfunction "2_2") (pintype "passive"))
      (node (ref "C78") (pin "2") (pinfunction "2_2") (pintype "passive"))
      (node (ref "TP90") (pin "TP") (pinfunction "TP_TP") (pintype "passive"))
      (node (ref "U7") (pin "5") (pinfunction "TXOUT_5") (pintype "passive"))
    )
    (net (code "20") (name "/VOUT1") (class "Default")
      (node (ref "C67") (pin "2") (pinfunction "2_2") (pintype "passive"))
      (node (ref "C70") (pin "2") (pinfunction "2_2") (pintype "passive"))
      (node (ref "TP83") (pin "TP") (pinfunction "TP_TP") (pintype "passive"))
      (node (ref "U7") (pin "32") (pinfunction "VDDX_32") (pintype "passive"))
    )
    (net (code "21") (name "/VOUT2") (class "Default")
      (node (ref "C68") (pin "2") (pinfunction "2_2") (pintype "passive"))
      (node (ref "C69") (pin "2") (pinfunction "2_2") (pintype "passive"))
      (node (ref "TP82") (pin "TP") (pinfunction "TP_TP") (pintype "passive"))
      (node (ref "U7") (pin "1") (pinfunction "VDDA_1") (pintype "passive"))
    )
    (net (code "22") (name "/VRFIN") (class "Default")
      (node (ref "C73") (pin "2") (pinfunction "2_2") (pintype "passive"))
      (node (ref "C76") (pin "2") (pinfunction "2_2") (pintype "passive"))
      (node (ref "R32") (pin "1") (pintype "passive"))
      (node (ref "TP89") (pin "TP") (pinfunction "TP_TP") (pintype "passive"))
      (node (ref "U7") (pin "4") (pinfunction "VDDPA_4") (pintype "passive"))
    )
    (net (code "23") (name "/VRFOUT") (class "Default")
      (node (ref "R32") (pin "2") (pintype "passive"))
      (node (ref "TP88") (pin "TP") (pinfunction "TP_TP") (pintype "passive"))
      (node (ref "U7") (pin "3") (pinfunction "VDDRF_3") (pintype "passive"))
    )
    (net (code "24") (name "GND") (class "Default")
      (node (ref "C58") (pin "1") (pinfunction "1_1") (pintype "passive"))
      (node (ref "C59") (pin "1") (pinfunction "1_1") (pintype "passive"))
      (node (ref "C60") (pin "1") (pinfunction "1_1") (pintype "passive"))
      (node (ref "C61") (pin "1") (pinfunction "1_1") (pintype "passive"))
      (node (ref "C62") (pin "1") (pinfunction "1_1") (pintype "passive"))
      (node (ref "C63") (pin "2") (pinfunction "2_2") (pintype "passive"))
      (node (ref "C64") (pin "2") (pinfunction "2_2") (pintype "passive"))
      (node (ref "C65") (pin "1") (pinfunction "1_1") (pintype "passive"))
      (node (ref "C66") (pin "1") (pinfunction "1_1") (pintype "passive"))
      (node (ref "C67") (pin "1") (pinfunction "1_1") (pintype "passive"))
      (node (ref "C68") (pin "1") (pinfunction "1_1") (pintype "passive"))
      (node (ref "C69") (pin "1") (pinfunction "1_1") (pintype "passive"))
      (node (ref "C70") (pin "1") (pinfunction "1_1") (pintype "passive"))
      (node (ref "C71") (pin "1") (pinfunction "1_1") (pintype "passive"))
      (node (ref "C72") (pin "1") (pinfunction "1_1") (pintype "passive"))
      (node (ref "C73") (pin "1") (pinfunction "1_1") (pintype "passive"))
      (node (ref "C74") (pin "1") (pinfunction "1_1") (pintype "passive"))
      (node (ref "C75") (pin "1") (pinfunction "1_1") (pintype "passive"))
      (node (ref "C76") (pin "1") (pinfunction "1_1") (pintype "passive"))
      (node (ref "C79") (pin "2") (pinfunction "2_2") (pintype "passive"))
      (node (ref "C80") (pin "1") (pinfunction "1_1") (pintype "passive"))
      (node (ref "C82") (pin "1") (pinfunction "1_1") (pintype "passive"))
      (node (ref "C83") (pin "2") (pinfunction "2_2") (pintype "passive"))
      (node (ref "C84") (pin "2") (pinfunction "2_2") (pintype "passive"))
      (node (ref "C85") (pin "1") (pinfunction "1_1") (pintype "passive"))
      (node (ref "C86") (pin "1") (pinfunction "1_1") (pintype "passive"))
      (node (ref "C87") (pin "1") (pinfunction "1_1") (pintype "passive"))
      (node (ref "C88") (pin "1") (pinfunction "1_1") (pintype "passive"))
      (node (ref "C89") (pin "1") (pinfunction "1_1") (pintype "passive"))
      (node (ref "C92") (pin "1") (pinfunction "1_1") (pintype "passive"))
      (node (ref "C93") (pin "1") (pinfunction "1_1") (pintype "passive"))
      (node (ref "C96") (pin "1") (pinfunction "1_1") (pintype "passive"))
      (node (ref "C97") (pin "2") (pinfunction "2_2") (pintype "passive"))
      (node (ref "C98") (pin "2") (pinfunction "2_2") (pintype "passive"))
      (node (ref "NT1") (pin "1") (pintype "passive"))
      (node (ref "Q1") (pin "S") (pinfunction "S_S") (pintype "passive"))
      (node (ref "R28") (pin "1") (pintype "passive"))
      (node (ref "R30") (pin "1") (pintype "passive"))
      (node (ref "R35") (pin "1") (pintype "passive"))
      (node (ref "R39") (pin "1") (pintype "passive"))
      (node (ref "TP102") (pin "TP") (pinfunction "TP_TP") (pintype "passive"))
      (node (ref "TP103") (pin "TP") (pinfunction "TP_TP") (pintype "passive"))
      (node (ref "U7") (pin "10") (pinfunction "VSS_10") (pintype "passive"))
      (node (ref "U7") (pin "15") (pinfunction "VSSA_15") (pintype "passive"))
      (node (ref "U7") (pin "17") (pinfunction "IO0_17") (pintype "passive"))
      (node (ref "U7") (pin "25") (pinfunction "EN2_25") (pintype "passive"))
      (node (ref "U7") (pin "29") (pinfunction "VSSD_29") (pintype "passive"))
      (node (ref "U7") (pin "33") (pinfunction "PAD_33") (pintype "passive"))
      (node (ref "U7") (pin "6") (pinfunction "VSSPA_6") (pintype "passive"))
      (node (ref "U7") (pin "7") (pinfunction "VSSRX_7") (pintype "passive"))
      (node (ref "X2") (pin "2") (pinfunction "2_2") (pintype "passive"))
      (node (ref "X2") (pin "4") (pinfunction "4_4") (pintype "passive"))
    )
    (net (code "25") (name "Net-(C77-Pad1)") (class "Default")
      (node (ref "C77") (pin "1") (pinfunction "1_1") (pintype "passive"))
      (node (ref "C78") (pin "1") (pinfunction "1_1") (pintype "passive"))
      (node (ref "L4") (pin "1") (pinfunction "1_1") (pintype "passive"))
      (node (ref "TP91") (pin "TP") (pinfunction "TP_TP") (pintype "passive"))
    )
    (net (code "26") (name "Net-(C81-Pad2)") (class "Default")
      (node (ref "C81") (pin "2") (pinfunction "2_2") (pintype "passive"))
      (node (ref "C87") (pin "2") (pinfunction "2_2") (pintype "passive"))
      (node (ref "C89") (pin "2") (pinfunction "2_2") (pintype "passive"))
      (node (ref "C90") (pin "1") (pinfunction "1_1") (pintype "passive"))
      (node (ref "L4") (pin "2") (pinfunction "2_2") (pintype "passive"))
      (node (ref "L5") (pin "1") (pinfunction "1_1") (pintype "passive"))
      (node (ref "TP94") (pin "TP") (pinfunction "TP_TP") (pintype "passive"))
    )
    (net (code "27") (name "Net-(C90-Pad2)") (class "Default")
      (node (ref "C90") (pin "2") (pinfunction "2_2") (pintype "passive"))
      (node (ref "C91") (pin "2") (pinfunction "2_2") (pintype "passive"))
      (node (ref "C93") (pin "2") (pinfunction "2_2") (pintype "passive"))
      (node (ref "C96") (pin "2") (pinfunction "2_2") (pintype "passive"))
      (node (ref "L5") (pin "2") (pinfunction "2_2") (pintype "passive"))
      (node (ref "R36") (pin "1") (pintype "passive"))
      (node (ref "TP97") (pin "TP") (pinfunction "TP_TP") (pintype "passive"))
    )
    (net (code "28") (name "Net-(C94-Pad2)") (class "Default")
      (node (ref "C94") (pin "2") (pinfunction "2_2") (pintype "passive"))
      (node (ref "C95") (pin "2") (pinfunction "2_2") (pintype "passive"))
      (node (ref "R37") (pin "2") (pintype "passive"))
      (node (ref "TP98") (pin "TP") (pinfunction "TP_TP") (pintype "passive"))
    )
    (net (code "29") (name "Net-(LED1-PadA)") (class "Default")
      (node (ref "LED1") (pin "A") (pinfunction "A_A") (pintype "passive"))
      (node (ref "R34") (pin "1") (pintype "passive"))
      (node (ref "TP95") (pin "TP") (pinfunction "TP_TP") (pintype "passive"))
    )
    (net (code "30") (name "Net-(LED1-PadK)") (class "Default")
      (node (ref "LED1") (pin "K") (pinfunction "K_K") (pintype "passive"))
      (node (ref "Q1") (pin "D") (pinfunction "D_D") (pintype "passive"))
    )
    (net (code "31") (name "Net-(R36-Pad2)") (class "Default")
      (node (ref "R36") (pin "2") (pintype "passive"))
      (node (ref "R37") (pin "1") (pintype "passive"))
      (node (ref "TP99") (pin "TP") (pinfunction "TP_TP") (pintype "passive"))
    )
    (net (code "32") (name "Net-(U7-DATA_CLK)") (class "Default")
      (node (ref "C64") (pin "1") (pinfunction "1_1") (pintype "passive"))
      (node (ref "R29") (pin "1") (pintype "passive"))
      (node (ref "TP85") (pin "TP") (pinfunction "TP_TP") (pintype "passive"))
      (node (ref "U7") (pin "26") (pinfunction "DATA_CLK_26") (pintype "passive"))
    )
    (net (code "33") (name "Net-(U7-IO6)") (class "Default")
      (node (ref "C71") (pin "2") (pinfunction "2_2") (pintype "passive"))
      (node (ref "R33") (pin "1") (pintype "passive"))
      (node (ref "TP87") (pin "TP") (pinfunction "TP_TP") (pintype "passive"))
      (node (ref "U7") (pin "23") (pinfunction "IO6_23") (pintype "passive"))
    )
    (net (code "34") (name "Net-(U7-IO7)") (class "Default")
      (node (ref "C72") (pin "2") (pinfunction "2_2") (pintype "passive"))
      (node (ref "R31") (pin "1") (pintype "passive"))
      (node (ref "TP86") (pin "TP") (pinfunction "TP_TP") (pintype "passive"))
      (node (ref "U7") (pin "24") (pinfunction "IO7_24") (pintype "passive"))
    )
    (net (code "35") (name "Net-(U7-OSC_IN)") (class "Default")
      (node (ref "C58") (pin "2") (pinfunction "2_2") (pintype "passive"))
      (node (ref "U7") (pin "31") (pinfunction "OSC_IN_31") (pintype "passive"))
      (node (ref "X2") (pin "3") (pinfunction "3_3") (pintype "passive"))
    )
    (net (code "36") (name "Net-(U7-OSC_OUT)") (class "Default")
      (node (ref "C59") (pin "2") (pinfunction "2_2") (pintype "passive"))
      (node (ref "U7") (pin "30") (pinfunction "OSC_OUT_30") (pintype "passive"))
      (node (ref "X2") (pin "1") (pinfunction "1_1") (pintype "passive"))
    )
    (net (code "37") (name "unconnected-(ANT1-Pad1)") (class "Default")
      (node (ref "ANT1") (pin "1") (pinfunction "1_1") (pintype "passive"))
    )
    (net (code "38") (name "unconnected-(ANT1-Pad2)") (class "Default")
      (node (ref "ANT1") (pin "2") (pinfunction "2_2") (pintype "passive"))
    )
    (net (code "39") (name "unconnected-(NT1-Pad2)") (class "Default")
      (node (ref "NT1") (pin "2") (pintype "passive"))
    )
    (net (code "40") (name "unconnected-(U7-IO3-Pad20)") (class "Default")
      (node (ref "U7") (pin "20") (pinfunction "IO3_20") (pintype "passive"))
    )
    (net (code "41") (name "unconnected-(U7-IO5-Pad22)") (class "Default")
      (node (ref "U7") (pin "22") (pinfunction "IO5_22") (pintype "passive"))
    )
  )
)
